# C64toUSBKeyboard.net
KiCad netlist of a schematic drawn in EAGLE
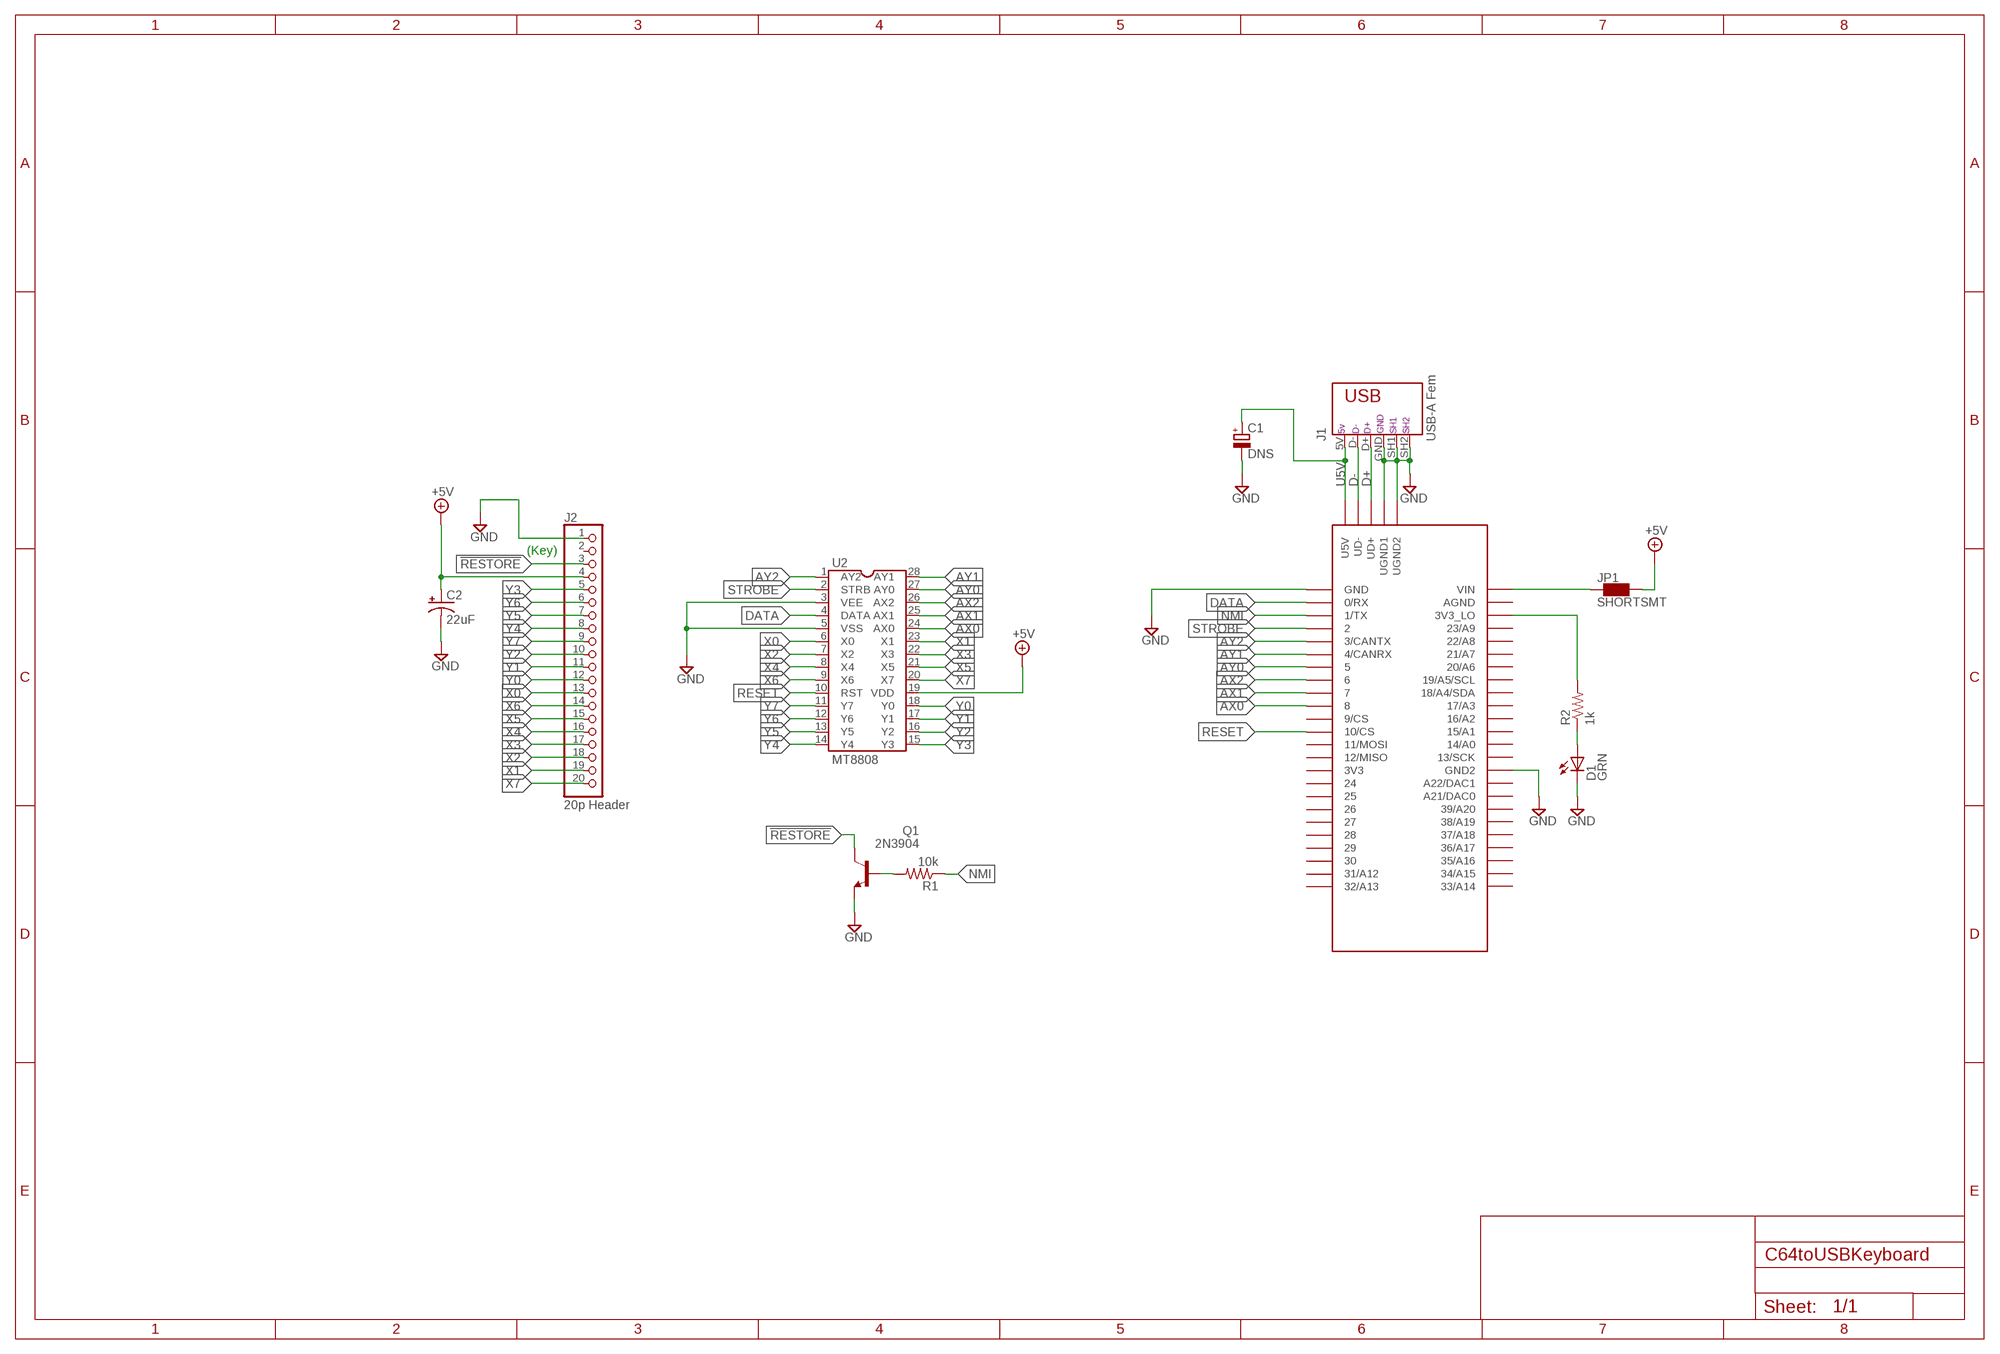
[diagram p0: schematic, sheet 1]

(export (version "E")
  (design (tool "Eeschema 10.0.6"))
  (components
    (comp (ref "C1")
      (value "DNS")
      (footprint "eagle-import:A_3216-18W")
      (libsource (lib "eagle-import") (part "CPOL-EUA/3216-18W"))
    )
    (comp (ref "C2")
      (value "22uF")
      (footprint "eagle-import:E2,5-6")
      (libsource (lib "eagle-import") (part "CPOL-USE2.5-6"))
    )
    (comp (ref "D1")
      (value "GRN")
      (footprint "eagle-import:LED-3MM-PTH")
      (libsource (lib "eagle-import") (part "LED-3MM-GRN"))
    )
    (comp (ref "J1")
      (value "USB-A Fem")
      (footprint "eagle-import:USB")
      (libsource (lib "eagle-import") (part "USB-787616"))
    )
    (comp (ref "J2")
      (value "20p Header")
      (footprint "eagle-import:1X20_ROUND")
      (libsource (lib "eagle-import") (part "HEADER-1X20ROUND"))
    )
    (comp (ref "JP1")
      (value "SHORTSMT")
      (footprint "eagle-import:SHORT")
      (libsource (lib "eagle-import") (part "SHORTSMT"))
    )
    (comp (ref "Q1")
      (value "2N3904")
      (footprint "eagle-import:TO92")
      (libsource (lib "eagle-import") (part "2N3904"))
    )
    (comp (ref "R1")
      (value "10k")
      (footprint "eagle-import:0207_10")
      (libsource (lib "eagle-import") (part "R-US_0207/10"))
    )
    (comp (ref "R2")
      (value "1k")
      (footprint "eagle-import:0207_10")
      (libsource (lib "eagle-import") (part "R-US_0207/10"))
    )
    (comp (ref "U1")
      (value "TEENSY_3.6_4.1")
      (footprint "eagle-import:TEENSY_3.5_3.6")
      (libsource (lib "eagle-import") (part "TEENSY_3.5/3.6"))
    )
    (comp (ref "U2")
      (value "MT8808")
      (footprint "eagle-import:DIL28-6")
      (libsource (lib "eagle-import") (part "DIL28"))
    )
  )
  (nets
    (net (code "1") (name "+5V") (class "Default")
      (node (ref "C2") (pin "+") (pinfunction "+_+") (pintype "passive"))
      (node (ref "J2") (pin "4") (pinfunction "4_4") (pintype "passive"))
      (node (ref "JP1") (pin "2") (pinfunction "2_2") (pintype "passive"))
      (node (ref "U2") (pin "19") (pinfunction "VDD_19") (pintype "passive"))
    )
    (net (code "2") (name "/D+") (class "Default")
      (node (ref "J1") (pin "D+") (pinfunction "3_D+") (pintype "passive"))
      (node (ref "U1") (pin "UD+") (pinfunction "UD+_UD+") (pintype "bidirectional"))
    )
    (net (code "3") (name "/D-") (class "Default")
      (node (ref "J1") (pin "D-") (pinfunction "2_D-") (pintype "passive"))
      (node (ref "U1") (pin "UD-") (pinfunction "UD-_UD-") (pintype "bidirectional"))
    )
    (net (code "4") (name "/U5V") (class "Default")
      (node (ref "C1") (pin "+") (pinfunction "+_+") (pintype "passive"))
      (node (ref "J1") (pin "5V") (pinfunction "1_5V") (pintype "passive"))
      (node (ref "U1") (pin "U5V") (pinfunction "U5V_U5V") (pintype "bidirectional"))
    )
    (net (code "5") (name "/~{RESTORE}") (class "Default")
      (node (ref "J2") (pin "3") (pinfunction "3_3") (pintype "passive"))
      (node (ref "Q1") (pin "1") (pinfunction "C_1") (pintype "passive"))
    )
    (net (code "6") (name "AX0") (class "Default")
      (node (ref "U1") (pin "8") (pinfunction "8_8") (pintype "bidirectional"))
      (node (ref "U2") (pin "24") (pinfunction "AX0_24") (pintype "passive"))
    )
    (net (code "7") (name "AX1") (class "Default")
      (node (ref "U1") (pin "7") (pinfunction "7_7") (pintype "bidirectional"))
      (node (ref "U2") (pin "25") (pinfunction "AX1_25") (pintype "passive"))
    )
    (net (code "8") (name "AX2") (class "Default")
      (node (ref "U1") (pin "6") (pinfunction "6_6") (pintype "bidirectional"))
      (node (ref "U2") (pin "26") (pinfunction "AX2_26") (pintype "passive"))
    )
    (net (code "9") (name "AY0") (class "Default")
      (node (ref "U1") (pin "5") (pinfunction "5_5") (pintype "bidirectional"))
      (node (ref "U2") (pin "27") (pinfunction "AY0_27") (pintype "passive"))
    )
    (net (code "10") (name "AY1") (class "Default")
      (node (ref "U1") (pin "4/CANRX") (pinfunction "4/CANRX_4/CANRX") (pintype "bidirectional"))
      (node (ref "U2") (pin "28") (pinfunction "AY1_28") (pintype "passive"))
    )
    (net (code "11") (name "AY2") (class "Default")
      (node (ref "U1") (pin "3/CANTX") (pinfunction "3/CANTX_3/CANTX") (pintype "bidirectional"))
      (node (ref "U2") (pin "1") (pinfunction "AY2_1") (pintype "passive"))
    )
    (net (code "12") (name "DATA") (class "Default")
      (node (ref "U1") (pin "0/RX") (pinfunction "0/RX_0/RX") (pintype "bidirectional"))
      (node (ref "U2") (pin "4") (pinfunction "DATA_4") (pintype "passive"))
    )
    (net (code "13") (name "GND") (class "Default")
      (node (ref "C1") (pin "-") (pinfunction "-_-") (pintype "passive"))
      (node (ref "C2") (pin "-") (pinfunction "-_-") (pintype "passive"))
      (node (ref "D1") (pin "K") (pinfunction "C_K") (pintype "passive"))
      (node (ref "J1") (pin "GND") (pinfunction "4_GND") (pintype "passive"))
      (node (ref "J1") (pin "SH1") (pinfunction "5_SH1") (pintype "passive"))
      (node (ref "J1") (pin "SH2") (pinfunction "6_SH2") (pintype "passive"))
      (node (ref "J2") (pin "1") (pinfunction "1_1") (pintype "passive"))
      (node (ref "Q1") (pin "3") (pinfunction "E_3") (pintype "passive"))
      (node (ref "U1") (pin "GND") (pinfunction "GND_GND") (pintype "bidirectional"))
      (node (ref "U1") (pin "GND2") (pinfunction "GND2_GND2") (pintype "bidirectional"))
      (node (ref "U1") (pin "UGND1") (pinfunction "UGND1_UGND1") (pintype "bidirectional"))
      (node (ref "U1") (pin "UGND2") (pinfunction "UGND2_UGND2") (pintype "bidirectional"))
      (node (ref "U2") (pin "3") (pinfunction "VEE_3") (pintype "passive"))
      (node (ref "U2") (pin "5") (pinfunction "VSS_5") (pintype "passive"))
    )
    (net (code "14") (name "NMI") (class "Default")
      (node (ref "R1") (pin "1") (pinfunction "1_1") (pintype "passive"))
      (node (ref "U1") (pin "1/TX") (pinfunction "1/TX_1/TX") (pintype "bidirectional"))
    )
    (net (code "15") (name "Net-(D1-PadA)") (class "Default")
      (node (ref "D1") (pin "A") (pinfunction "A_A") (pintype "passive"))
      (node (ref "R2") (pin "1") (pinfunction "1_1") (pintype "passive"))
    )
    (net (code "16") (name "Net-(JP1-Pad1)") (class "Default")
      (node (ref "JP1") (pin "1") (pinfunction "1_1") (pintype "passive"))
      (node (ref "U1") (pin "VIN") (pinfunction "VIN_VIN") (pintype "bidirectional"))
    )
    (net (code "17") (name "Net-(Q1-B)") (class "Default")
      (node (ref "Q1") (pin "2") (pinfunction "B_2") (pintype "passive"))
      (node (ref "R1") (pin "2") (pinfunction "2_2") (pintype "passive"))
    )
    (net (code "18") (name "Net-(R2-Pad2)") (class "Default")
      (node (ref "R2") (pin "2") (pinfunction "2_2") (pintype "passive"))
      (node (ref "U1") (pin "3V3_LO") (pinfunction "3V3_LO_3V3_LO") (pintype "bidirectional"))
    )
    (net (code "19") (name "RESET") (class "Default")
      (node (ref "U1") (pin "10/CS") (pinfunction "10/CS_10/CS") (pintype "bidirectional"))
      (node (ref "U2") (pin "10") (pinfunction "RST_10") (pintype "passive"))
    )
    (net (code "20") (name "STROBE") (class "Default")
      (node (ref "U1") (pin "2") (pinfunction "2_2") (pintype "bidirectional"))
      (node (ref "U2") (pin "2") (pinfunction "STRB_2") (pintype "passive"))
    )
    (net (code "21") (name "X0") (class "Default")
      (node (ref "J2") (pin "13") (pinfunction "13_13") (pintype "passive"))
      (node (ref "U2") (pin "6") (pinfunction "X0_6") (pintype "passive"))
    )
    (net (code "22") (name "X1") (class "Default")
      (node (ref "J2") (pin "19") (pinfunction "19_19") (pintype "passive"))
      (node (ref "U2") (pin "23") (pinfunction "X1_23") (pintype "passive"))
    )
    (net (code "23") (name "X2") (class "Default")
      (node (ref "J2") (pin "18") (pinfunction "18_18") (pintype "passive"))
      (node (ref "U2") (pin "7") (pinfunction "X2_7") (pintype "passive"))
    )
    (net (code "24") (name "X3") (class "Default")
      (node (ref "J2") (pin "17") (pinfunction "17_17") (pintype "passive"))
      (node (ref "U2") (pin "22") (pinfunction "X3_22") (pintype "passive"))
    )
    (net (code "25") (name "X4") (class "Default")
      (node (ref "J2") (pin "16") (pinfunction "16_16") (pintype "passive"))
      (node (ref "U2") (pin "8") (pinfunction "X4_8") (pintype "passive"))
    )
    (net (code "26") (name "X5") (class "Default")
      (node (ref "J2") (pin "15") (pinfunction "15_15") (pintype "passive"))
      (node (ref "U2") (pin "21") (pinfunction "X5_21") (pintype "passive"))
    )
    (net (code "27") (name "X6") (class "Default")
      (node (ref "J2") (pin "14") (pinfunction "14_14") (pintype "passive"))
      (node (ref "U2") (pin "9") (pinfunction "X6_9") (pintype "passive"))
    )
    (net (code "28") (name "X7") (class "Default")
      (node (ref "J2") (pin "20") (pinfunction "20_20") (pintype "passive"))
      (node (ref "U2") (pin "20") (pinfunction "X7_20") (pintype "passive"))
    )
    (net (code "29") (name "Y0") (class "Default")
      (node (ref "J2") (pin "12") (pinfunction "12_12") (pintype "passive"))
      (node (ref "U2") (pin "18") (pinfunction "Y0_18") (pintype "passive"))
    )
    (net (code "30") (name "Y1") (class "Default")
      (node (ref "J2") (pin "11") (pinfunction "11_11") (pintype "passive"))
      (node (ref "U2") (pin "17") (pinfunction "Y1_17") (pintype "passive"))
    )
    (net (code "31") (name "Y2") (class "Default")
      (node (ref "J2") (pin "10") (pinfunction "10_10") (pintype "passive"))
      (node (ref "U2") (pin "16") (pinfunction "Y2_16") (pintype "passive"))
    )
    (net (code "32") (name "Y3") (class "Default")
      (node (ref "J2") (pin "5") (pinfunction "5_5") (pintype "passive"))
      (node (ref "U2") (pin "15") (pinfunction "Y3_15") (pintype "passive"))
    )
    (net (code "33") (name "Y4") (class "Default")
      (node (ref "J2") (pin "8") (pinfunction "8_8") (pintype "passive"))
      (node (ref "U2") (pin "14") (pinfunction "Y4_14") (pintype "passive"))
    )
    (net (code "34") (name "Y5") (class "Default")
      (node (ref "J2") (pin "7") (pinfunction "7_7") (pintype "passive"))
      (node (ref "U2") (pin "13") (pinfunction "Y5_13") (pintype "passive"))
    )
    (net (code "35") (name "Y6") (class "Default")
      (node (ref "J2") (pin "6") (pinfunction "6_6") (pintype "passive"))
      (node (ref "U2") (pin "12") (pinfunction "Y6_12") (pintype "passive"))
    )
    (net (code "36") (name "Y7") (class "Default")
      (node (ref "J2") (pin "9") (pinfunction "9_9") (pintype "passive"))
      (node (ref "U2") (pin "11") (pinfunction "Y7_11") (pintype "passive"))
    )
    (net (code "37") (name "unconnected-(J2-Pad2)") (class "Default")
      (node (ref "J2") (pin "2") (pinfunction "2_2") (pintype "passive"))
    )
    (net (code "38") (name "unconnected-(U1-A21{slash}DAC0-Pad21{slash}DAC0)") (class "Default")
      (node (ref "U1") (pin "21/DAC0") (pinfunction "A21/DAC0_21/DAC0") (pintype "bidirectional"))
    )
    (net (code "39") (name "unconnected-(U1-Pad3V3)") (class "Default")
      (node (ref "U1") (pin "3V3") (pinfunction "3V3_3V3") (pintype "bidirectional"))
    )
    (net (code "40") (name "unconnected-(U1-Pad9{slash}CS)") (class "Default")
      (node (ref "U1") (pin "9/CS") (pinfunction "9/CS_9/CS") (pintype "bidirectional"))
    )
    (net (code "41") (name "unconnected-(U1-Pad11{slash}MOSI)") (class "Default")
      (node (ref "U1") (pin "11/MOSI") (pinfunction "11/MOSI_11/MOSI") (pintype "bidirectional"))
    )
    (net (code "42") (name "unconnected-(U1-Pad12{slash}MISO)") (class "Default")
      (node (ref "U1") (pin "12/MISO") (pinfunction "12/MISO_12/MISO") (pintype "bidirectional"))
    )
    (net (code "43") (name "unconnected-(U1-Pad13{slash}SCK)") (class "Default")
      (node (ref "U1") (pin "13/SCK") (pinfunction "13/SCK_13/SCK") (pintype "bidirectional"))
    )
    (net (code "44") (name "unconnected-(U1-Pad14{slash}A0)") (class "Default")
      (node (ref "U1") (pin "14/A0") (pinfunction "14/A0_14/A0") (pintype "bidirectional"))
    )
    (net (code "45") (name "unconnected-(U1-Pad15{slash}A1)") (class "Default")
      (node (ref "U1") (pin "15/A1") (pinfunction "15/A1_15/A1") (pintype "bidirectional"))
    )
    (net (code "46") (name "unconnected-(U1-Pad16{slash}A2)") (class "Default")
      (node (ref "U1") (pin "16/A2") (pinfunction "16/A2_16/A2") (pintype "bidirectional"))
    )
    (net (code "47") (name "unconnected-(U1-Pad17{slash}A3)") (class "Default")
      (node (ref "U1") (pin "17/A3") (pinfunction "17/A3_17/A3") (pintype "bidirectional"))
    )
    (net (code "48") (name "unconnected-(U1-Pad18{slash}A4{slash}SDA)") (class "Default")
      (node (ref "U1") (pin "18/A4/SDA") (pinfunction "18/A4/SDA_18/A4/SDA") (pintype "bidirectional"))
    )
    (net (code "49") (name "unconnected-(U1-Pad19{slash}A5{slash}SCL)") (class "Default")
      (node (ref "U1") (pin "19/A5/SCL") (pinfunction "19/A5/SCL_19/A5/SCL") (pintype "bidirectional"))
    )
    (net (code "50") (name "unconnected-(U1-Pad20{slash}A6)") (class "Default")
      (node (ref "U1") (pin "20/A6") (pinfunction "20/A6_20/A6") (pintype "bidirectional"))
    )
    (net (code "51") (name "unconnected-(U1-Pad21{slash}A7)") (class "Default")
      (node (ref "U1") (pin "21/A7") (pinfunction "21/A7_21/A7") (pintype "bidirectional"))
    )
    (net (code "52") (name "unconnected-(U1-Pad22{slash}A8)") (class "Default")
      (node (ref "U1") (pin "22/A8") (pinfunction "22/A8_22/A8") (pintype "bidirectional"))
    )
    (net (code "53") (name "unconnected-(U1-Pad23{slash}A9)") (class "Default")
      (node (ref "U1") (pin "23/A9") (pinfunction "23/A9_23/A9") (pintype "bidirectional"))
    )
    (net (code "54") (name "unconnected-(U1-Pad24)") (class "Default")
      (node (ref "U1") (pin "24") (pinfunction "24_24") (pintype "bidirectional"))
    )
    (net (code "55") (name "unconnected-(U1-Pad25)") (class "Default")
      (node (ref "U1") (pin "25") (pinfunction "25_25") (pintype "bidirectional"))
    )
    (net (code "56") (name "unconnected-(U1-Pad26)") (class "Default")
      (node (ref "U1") (pin "26") (pinfunction "26_26") (pintype "bidirectional"))
    )
    (net (code "57") (name "unconnected-(U1-Pad27)") (class "Default")
      (node (ref "U1") (pin "27") (pinfunction "27_27") (pintype "bidirectional"))
    )
    (net (code "58") (name "unconnected-(U1-Pad28)") (class "Default")
      (node (ref "U1") (pin "28") (pinfunction "28_28") (pintype "bidirectional"))
    )
    (net (code "59") (name "unconnected-(U1-Pad29)") (class "Default")
      (node (ref "U1") (pin "29") (pinfunction "29_29") (pintype "bidirectional"))
    )
    (net (code "60") (name "unconnected-(U1-Pad30)") (class "Default")
      (node (ref "U1") (pin "30") (pinfunction "30_30") (pintype "bidirectional"))
    )
    (net (code "61") (name "unconnected-(U1-Pad31{slash}A12)") (class "Default")
      (node (ref "U1") (pin "31/A12") (pinfunction "31/A12_31/A12") (pintype "bidirectional"))
    )
    (net (code "62") (name "unconnected-(U1-Pad32{slash}A13)") (class "Default")
      (node (ref "U1") (pin "32/A13") (pinfunction "32/A13_32/A13") (pintype "bidirectional"))
    )
    (net (code "63") (name "unconnected-(U1-Pad33{slash}A14)") (class "Default")
      (node (ref "U1") (pin "33/A14") (pinfunction "33/A14_33/A14") (pintype "bidirectional"))
    )
    (net (code "64") (name "unconnected-(U1-Pad34{slash}A15)") (class "Default")
      (node (ref "U1") (pin "34/A15") (pinfunction "34/A15_34/A15") (pintype "bidirectional"))
    )
    (net (code "65") (name "unconnected-(U1-Pad35{slash}A16)") (class "Default")
      (node (ref "U1") (pin "35/A16") (pinfunction "35/A16_35/A16") (pintype "bidirectional"))
    )
    (net (code "66") (name "unconnected-(U1-Pad36{slash}A17)") (class "Default")
      (node (ref "U1") (pin "36/A17") (pinfunction "36/A17_36/A17") (pintype "bidirectional"))
    )
    (net (code "67") (name "unconnected-(U1-Pad37{slash}A18)") (class "Default")
      (node (ref "U1") (pin "37/A18") (pinfunction "37/A18_37/A18") (pintype "bidirectional"))
    )
    (net (code "68") (name "unconnected-(U1-Pad38{slash}A19)") (class "Default")
      (node (ref "U1") (pin "38/A19") (pinfunction "38/A19_38/A19") (pintype "bidirectional"))
    )
    (net (code "69") (name "unconnected-(U1-Pad39{slash}A20)") (class "Default")
      (node (ref "U1") (pin "39/A20") (pinfunction "39/A20_39/A20") (pintype "bidirectional"))
    )
    (net (code "70") (name "unconnected-(U1-PadA22{slash}DAC1)") (class "Default")
      (node (ref "U1") (pin "A22/DAC1") (pinfunction "A22/DAC1_A22/DAC1") (pintype "bidirectional"))
    )
    (net (code "71") (name "unconnected-(U1-PadAGND)") (class "Default")
      (node (ref "U1") (pin "AGND") (pinfunction "AGND_AGND") (pintype "bidirectional"))
    )
  )
)
